# BTsoundCard_R1.net
KiCad netlist of a schematic drawn in EAGLE
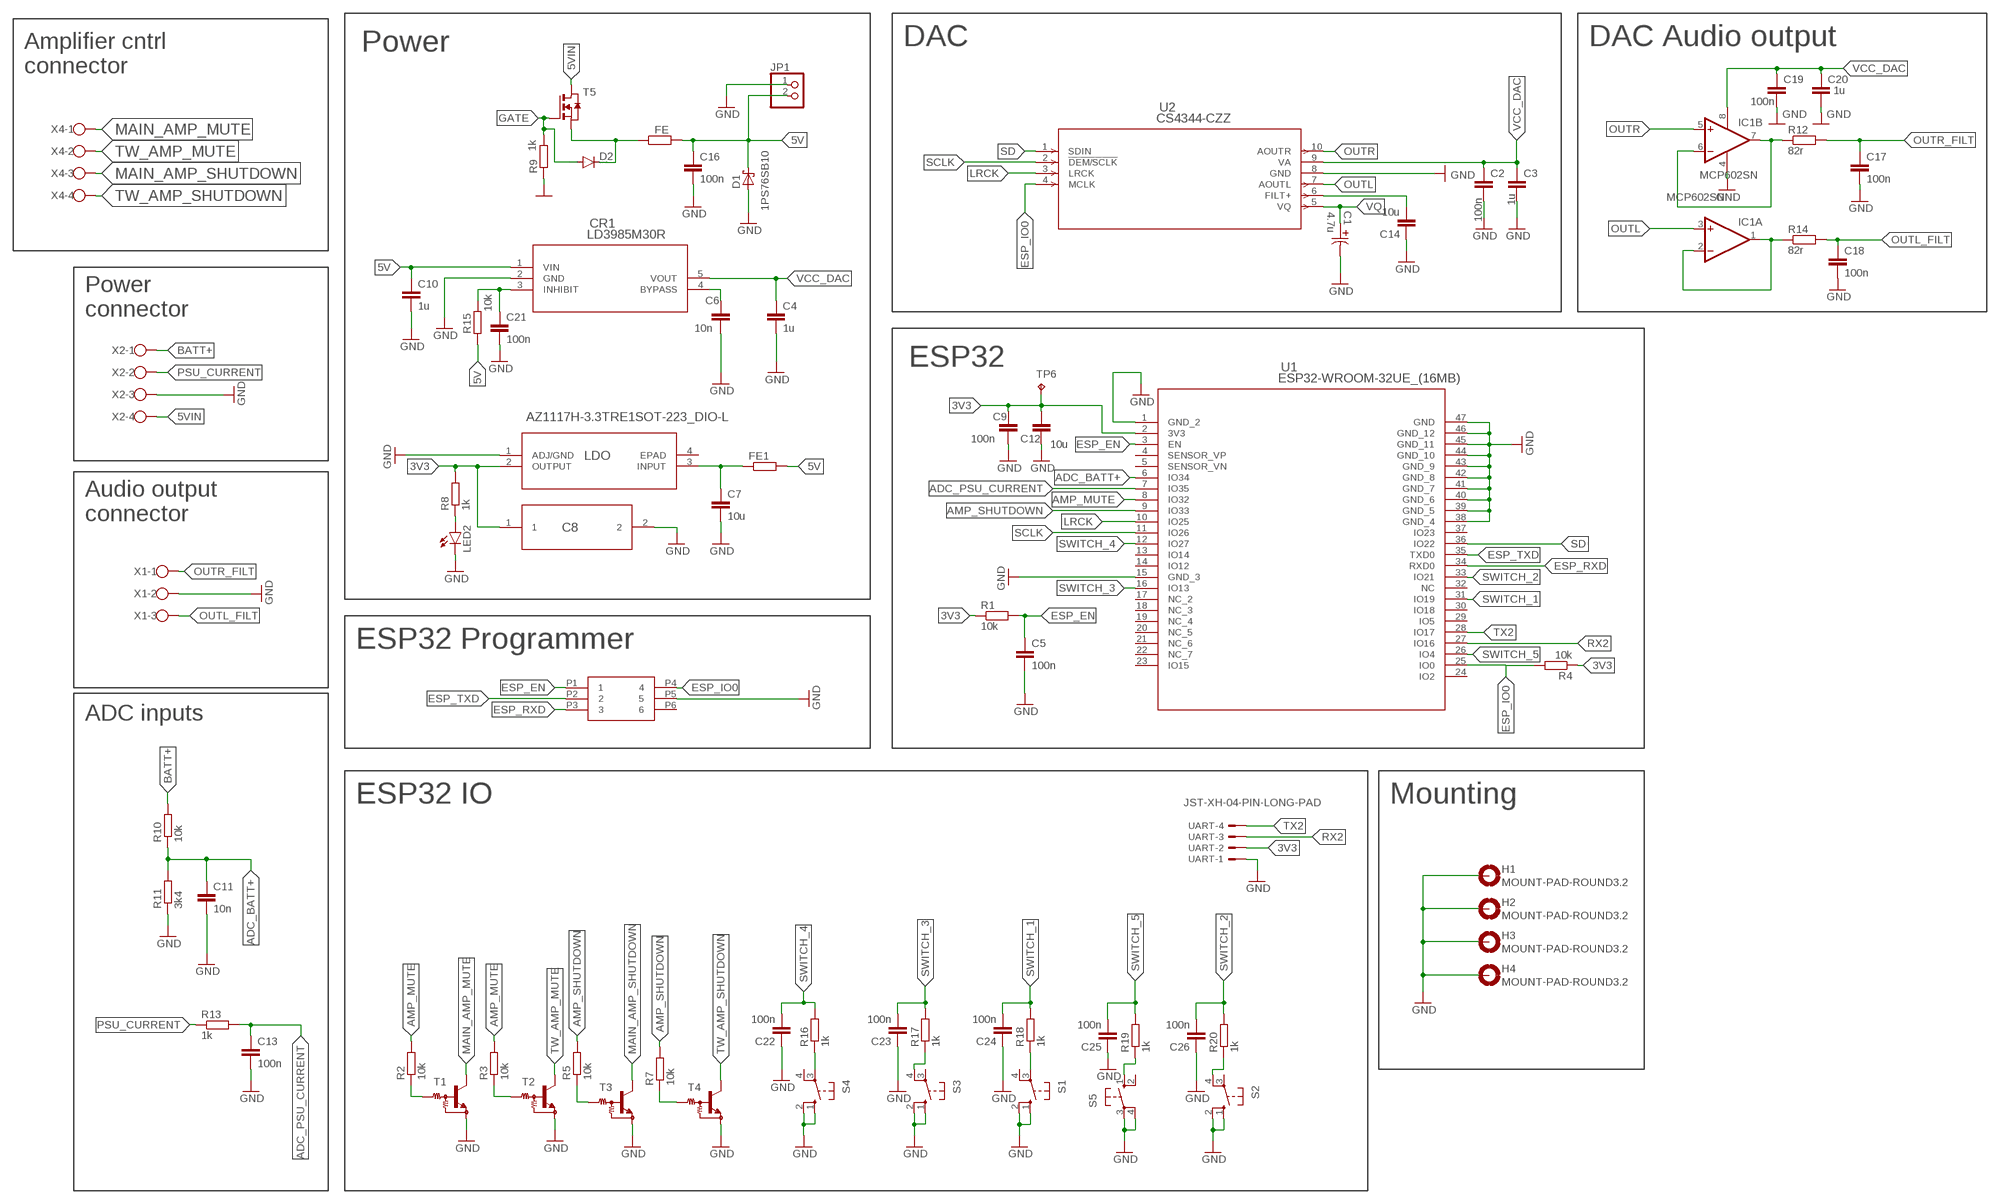
[diagram p0: schematic, sheet 1]

(export (version "E")
  (design (tool "Eeschema 10.0.6"))
  (components
    (comp (ref "C1")
      (value "4.7u")
      (footprint "eagle-import:CAP_EEFK_B_PAN-M")
      (fields (field (name "MANUFACTURER_PART_NUMBER") "EEEFK1H4R7R"))
      (libsource (lib "eagle-import") (part "EEEFK1H4R7RCAP_EEFK_B_PAN-M"))
    )
    (comp (ref "C2")
      (value "100n")
      (footprint "eagle-import:C0603")
      (libsource (lib "eagle-import") (part "C-EUC0603"))
    )
    (comp (ref "C3")
      (value "1u")
      (footprint "eagle-import:C0603")
      (libsource (lib "eagle-import") (part "C-EUC0603"))
    )
    (comp (ref "C4")
      (value "1u")
      (footprint "eagle-import:C0603")
      (libsource (lib "eagle-import") (part "C-EUC0603"))
    )
    (comp (ref "C5")
      (value "100n")
      (footprint "eagle-import:C0603")
      (libsource (lib "eagle-import") (part "C-EUC0603"))
    )
    (comp (ref "C6")
      (value "10n")
      (footprint "eagle-import:C0603")
      (libsource (lib "eagle-import") (part "C-EUC0603"))
    )
    (comp (ref "C7")
      (value "10u")
      (footprint "eagle-import:C0805")
      (libsource (lib "eagle-import") (part "C-EUC0805"))
    )
    (comp (ref "C8")
      (value "TPSC336K010R0375")
      (footprint "eagle-import:TPSC336K010R0375_AVX")
      (fields (field (name "COPYRIGHT") "Copyright (C) 2018 Accelerated Designs. All rights reserved"))
      (libsource (lib "eagle-import") (part "TPSC336K010R0375"))
    )
    (comp (ref "C9")
      (value "100n")
      (footprint "eagle-import:C0603")
      (libsource (lib "eagle-import") (part "C-EUC0603"))
    )
    (comp (ref "C10")
      (value "1u")
      (footprint "eagle-import:C0603")
      (libsource (lib "eagle-import") (part "C-EUC0603"))
    )
    (comp (ref "C11")
      (value "10n")
      (footprint "eagle-import:C0603")
      (libsource (lib "eagle-import") (part "C-EUC0603"))
    )
    (comp (ref "C12")
      (value "10u")
      (footprint "eagle-import:C0805")
      (libsource (lib "eagle-import") (part "C-EUC0805"))
    )
    (comp (ref "C13")
      (value "100n")
      (footprint "eagle-import:C0603")
      (libsource (lib "eagle-import") (part "C-EUC0603"))
    )
    (comp (ref "C14")
      (value "10u")
      (footprint "eagle-import:C0805")
      (libsource (lib "eagle-import") (part "C-EUC0805"))
    )
    (comp (ref "C16")
      (value "100n")
      (footprint "eagle-import:C0603")
      (libsource (lib "eagle-import") (part "C-EUC0603"))
    )
    (comp (ref "C17")
      (value "100n")
      (footprint "eagle-import:C0603")
      (libsource (lib "eagle-import") (part "C-EUC0603"))
    )
    (comp (ref "C18")
      (value "100n")
      (footprint "eagle-import:C0603")
      (libsource (lib "eagle-import") (part "C-EUC0603"))
    )
    (comp (ref "C19")
      (value "100n")
      (footprint "eagle-import:C0603")
      (libsource (lib "eagle-import") (part "C-EUC0603"))
    )
    (comp (ref "C20")
      (value "1u")
      (footprint "eagle-import:C0603")
      (libsource (lib "eagle-import") (part "C-EUC0603"))
    )
    (comp (ref "C21")
      (value "100n")
      (footprint "eagle-import:C0603")
      (libsource (lib "eagle-import") (part "C-EUC0603"))
    )
    (comp (ref "C22")
      (value "100n")
      (footprint "eagle-import:C0603")
      (libsource (lib "eagle-import") (part "C-EUC0603"))
    )
    (comp (ref "C23")
      (value "100n")
      (footprint "eagle-import:C0603")
      (libsource (lib "eagle-import") (part "C-EUC0603"))
    )
    (comp (ref "C24")
      (value "100n")
      (footprint "eagle-import:C0603")
      (libsource (lib "eagle-import") (part "C-EUC0603"))
    )
    (comp (ref "C25")
      (value "100n")
      (footprint "eagle-import:C0603")
      (libsource (lib "eagle-import") (part "C-EUC0603"))
    )
    (comp (ref "C26")
      (value "100n")
      (footprint "eagle-import:C0603")
      (libsource (lib "eagle-import") (part "C-EUC0603"))
    )
    (comp (ref "CR1")
      (value "LD3985M30R")
      (footprint "eagle-import:SOT23-5L_STM")
      (fields (field (name "COPYRIGHT") "Copyright (C) 2023 Ultra Librarian. All rights reserved."))
      (libsource (lib "eagle-import") (part "LD3985M30R"))
    )
    (comp (ref "D1")
      (value "1PS76SB10")
      (footprint "eagle-import:SOD323(F)")
      (libsource (lib "eagle-import") (part "1PS76SB10"))
    )
    (comp (ref "D2")
      (value "5.1V")
      (footprint "eagle-import:MINIMELF")
      (libsource (lib "eagle-import") (part "DIODE-MINIMELF"))
    )
    (comp (ref "FE")
      (value "R-EU_R0805")
      (footprint "eagle-import:R0805")
      (libsource (lib "eagle-import") (part "R-EU_R0805"))
    )
    (comp (ref "FE1")
      (value "R-EU_R0805")
      (footprint "eagle-import:R0805")
      (libsource (lib "eagle-import") (part "R-EU_R0805"))
    )
    (comp (ref "H1")
      (value "MOUNT-PAD-ROUND3.2")
      (footprint "eagle-import:3,2-PAD")
      (libsource (lib "eagle-import") (part "MOUNT-PAD-ROUND3.2"))
    )
    (comp (ref "H2")
      (value "MOUNT-PAD-ROUND3.2")
      (footprint "eagle-import:3,2-PAD")
      (libsource (lib "eagle-import") (part "MOUNT-PAD-ROUND3.2"))
    )
    (comp (ref "H3")
      (value "MOUNT-PAD-ROUND3.2")
      (footprint "eagle-import:3,2-PAD")
      (libsource (lib "eagle-import") (part "MOUNT-PAD-ROUND3.2"))
    )
    (comp (ref "H4")
      (value "MOUNT-PAD-ROUND3.2")
      (footprint "eagle-import:3,2-PAD")
      (libsource (lib "eagle-import") (part "MOUNT-PAD-ROUND3.2"))
    )
    (comp (ref "IC1")
      (value "MCP602SN")
      (footprint "eagle-import:SO08")
      (libsource (lib "eagle-import") (part "MCP602SN"))
    )
    (comp (ref "JP1")
      (value "PINHD-1X2")
      (footprint "eagle-import:1X02")
      (libsource (lib "eagle-import") (part "PINHD-1X2"))
    )
    (comp (ref "LDO")
      (value "AZ1117H-3.3TRE1SOT-223_DIO-L")
      (footprint "eagle-import:SOT-223_DIO-L")
      (fields (field (name "MANUFACTURER_PART_NUMBER") "AZ1117H-3.3TRE1"))
      (libsource (lib "eagle-import") (part "AZ1117H-3.3TRE1SOT-223_DIO-L"))
    )
    (comp (ref "LED2")
      (value "LEDCHIP-LED0603")
      (footprint "eagle-import:CHIP-LED0603")
      (libsource (lib "eagle-import") (part "LEDCHIP-LED0603"))
    )
    (comp (ref "R1")
      (value "10k")
      (footprint "eagle-import:R0603")
      (libsource (lib "eagle-import") (part "R-EU_R0603"))
    )
    (comp (ref "R2")
      (value "10k")
      (footprint "eagle-import:R0603")
      (libsource (lib "eagle-import") (part "R-EU_R0603"))
    )
    (comp (ref "R3")
      (value "10k")
      (footprint "eagle-import:R0603")
      (libsource (lib "eagle-import") (part "R-EU_R0603"))
    )
    (comp (ref "R4")
      (value "10k")
      (footprint "eagle-import:R0603")
      (libsource (lib "eagle-import") (part "R-EU_R0603"))
    )
    (comp (ref "R5")
      (value "10k")
      (footprint "eagle-import:R0603")
      (libsource (lib "eagle-import") (part "R-EU_R0603"))
    )
    (comp (ref "R7")
      (value "10k")
      (footprint "eagle-import:R0603")
      (libsource (lib "eagle-import") (part "R-EU_R0603"))
    )
    (comp (ref "R8")
      (value "1k")
      (footprint "eagle-import:R0603")
      (libsource (lib "eagle-import") (part "R-EU_R0603"))
    )
    (comp (ref "R9")
      (value "1k")
      (footprint "eagle-import:R1206")
      (libsource (lib "eagle-import") (part "R-EU_R1206"))
    )
    (comp (ref "R10")
      (value "10k")
      (footprint "eagle-import:R0805")
      (libsource (lib "eagle-import") (part "R-EU_R0805"))
    )
    (comp (ref "R11")
      (value "3k4")
      (footprint "eagle-import:R0603")
      (libsource (lib "eagle-import") (part "R-EU_R0603"))
    )
    (comp (ref "R12")
      (value "82r")
      (footprint "eagle-import:R1206")
      (libsource (lib "eagle-import") (part "R-EU_R1206"))
    )
    (comp (ref "R13")
      (value "1k")
      (footprint "eagle-import:R0603")
      (libsource (lib "eagle-import") (part "R-EU_R0603"))
    )
    (comp (ref "R14")
      (value "82r")
      (footprint "eagle-import:R1206")
      (libsource (lib "eagle-import") (part "R-EU_R1206"))
    )
    (comp (ref "R15")
      (value "10k")
      (footprint "eagle-import:R0603")
      (libsource (lib "eagle-import") (part "R-EU_R0603"))
    )
    (comp (ref "R16")
      (value "1k")
      (footprint "eagle-import:R0603")
      (libsource (lib "eagle-import") (part "R-EU_R0603"))
    )
    (comp (ref "R17")
      (value "1k")
      (footprint "eagle-import:R0603")
      (libsource (lib "eagle-import") (part "R-EU_R0603"))
    )
    (comp (ref "R18")
      (value "1k")
      (footprint "eagle-import:R0603")
      (libsource (lib "eagle-import") (part "R-EU_R0603"))
    )
    (comp (ref "R19")
      (value "1k")
      (footprint "eagle-import:R0603")
      (libsource (lib "eagle-import") (part "R-EU_R0603"))
    )
    (comp (ref "R20")
      (value "1k")
      (footprint "eagle-import:R0603")
      (libsource (lib "eagle-import") (part "R-EU_R0603"))
    )
    (comp (ref "S1")
      (value "10-XX")
      (footprint "eagle-import:B3F-10XX")
      (fields (field (name "MPN") "B3F-1000"))
      (libsource (lib "eagle-import") (part "10-XX"))
    )
    (comp (ref "S2")
      (value "10-XX")
      (footprint "eagle-import:B3F-10XX")
      (fields (field (name "MPN") "B3F-1000"))
      (libsource (lib "eagle-import") (part "10-XX"))
    )
    (comp (ref "S3")
      (value "10-XX")
      (footprint "eagle-import:B3F-10XX")
      (fields (field (name "MPN") "B3F-1000"))
      (libsource (lib "eagle-import") (part "10-XX"))
    )
    (comp (ref "S4")
      (value "10-XX")
      (footprint "eagle-import:B3F-10XX")
      (fields (field (name "MPN") "B3F-1000"))
      (libsource (lib "eagle-import") (part "10-XX"))
    )
    (comp (ref "S5")
      (value "10-XX")
      (footprint "eagle-import:B3F-10XX")
      (fields (field (name "MPN") "B3F-1000"))
      (libsource (lib "eagle-import") (part "10-XX"))
    )
    (comp (ref "T1")
      (value "MUN2212T1-NPN_DRIVER-SC59-BEC")
      (footprint "eagle-import:SC59-BEC")
      (libsource (lib "eagle-import") (part "-NPN_DRIVER-SC59-BECMUN2212T1"))
    )
    (comp (ref "T2")
      (value "MUN2212T1-NPN_DRIVER-SC59-BEC")
      (footprint "eagle-import:SC59-BEC")
      (libsource (lib "eagle-import") (part "-NPN_DRIVER-SC59-BECMUN2212T1"))
    )
    (comp (ref "T3")
      (value "MUN2212T1-NPN_DRIVER-SC59-BEC")
      (footprint "eagle-import:SC59-BEC")
      (libsource (lib "eagle-import") (part "-NPN_DRIVER-SC59-BECMUN2212T1"))
    )
    (comp (ref "T4")
      (value "MUN2212T1-NPN_DRIVER-SC59-BEC")
      (footprint "eagle-import:SC59-BEC")
      (libsource (lib "eagle-import") (part "-NPN_DRIVER-SC59-BECMUN2212T1"))
    )
    (comp (ref "T5")
      (value "NMOSSOT23")
      (footprint "eagle-import:SOT-23")
      (libsource (lib "eagle-import") (part "NMOSSOT23"))
    )
    (comp (ref "TP6")
      (value "TPPAD1-13")
      (footprint "eagle-import:P1-13")
      (libsource (lib "eagle-import") (part "TPPAD1-13"))
    )
    (comp (ref "U$3")
      (value "3X2")
      (footprint "eagle-import:2X3")
      (libsource (lib "eagle-import") (part "3X2"))
    )
    (comp (ref "U1")
      (value "ESP32-WROOM-32UE_(16MB)")
      (footprint "eagle-import:IC38_ESP32-WROOM-32UE_(16MB)_E")
      (fields
        (field (name "MANUFACTURER_PART_NUMBER") "ESP32-WROOM-32UE (16MB)")
        (field (name "COPYRIGHT") "Copyright (C) 2022 Ultra Librarian. All rights reserved.")
      )
      (libsource (lib "eagle-import") (part "ESP32-WROOM-32UE_(16MB)"))
    )
    (comp (ref "U2")
      (value "CS4344-CZZ")
      (footprint "eagle-import:CIR-TSSOP-10")
      (fields (field (name "COPYRIGHT") "Copyright (C) 2023 Ultra Librarian. All rights reserved."))
      (libsource (lib "eagle-import") (part "CS4344-CZZ"))
    )
    (comp (ref "UART")
      (value "JST-XH-04-PIN-LONG-PAD")
      (footprint "eagle-import:JST-XH-04-PACKAGE-LONG-PAD")
      (libsource (lib "eagle-import") (part "JST-XH-04-PIN-LONG-PAD"))
    )
    (comp (ref "X1")
      (value "W237-103")
      (footprint "eagle-import:W237-103")
      (fields (field (name "MPN") "237-103"))
      (libsource (lib "eagle-import") (part "W237-103"))
    )
    (comp (ref "X2")
      (value "W237-4")
      (footprint "eagle-import:W237-4")
      (libsource (lib "eagle-import") (part "W237-4"))
    )
    (comp (ref "X4")
      (value "W237-4")
      (footprint "eagle-import:W237-4")
      (libsource (lib "eagle-import") (part "W237-4"))
    )
  )
  (nets
    (net (code "1") (name "3V3") (class "Default")
      (node (ref "C12") (pin "2") (pinfunction "2_2") (pintype "passive"))
      (node (ref "C8") (pin "1") (pinfunction "1_1") (pintype "passive"))
      (node (ref "C9") (pin "1") (pinfunction "1_1") (pintype "passive"))
      (node (ref "LDO") (pin "2") (pinfunction "OUTPUT_2") (pintype "output"))
      (node (ref "R1") (pin "1") (pinfunction "1_1") (pintype "passive"))
      (node (ref "R4") (pin "1") (pinfunction "1_1") (pintype "passive"))
      (node (ref "R8") (pin "2") (pinfunction "2_2") (pintype "passive"))
      (node (ref "TP6") (pin "TP") (pinfunction "TP_TP") (pintype "input"))
      (node (ref "U1") (pin "2") (pinfunction "3V3_2") (pintype "passive"))
      (node (ref "UART") (pin "2") (pinfunction "S_2") (pintype "passive"))
    )
    (net (code "2") (name "5V") (class "Default")
      (node (ref "C10") (pin "1") (pinfunction "1_1") (pintype "passive"))
      (node (ref "C16") (pin "1") (pinfunction "1_1") (pintype "passive"))
      (node (ref "CR1") (pin "1") (pinfunction "VIN_1") (pintype "power_in"))
      (node (ref "D1") (pin "1") (pinfunction "K_1") (pintype "passive"))
      (node (ref "FE") (pin "2") (pinfunction "2_2") (pintype "passive"))
      (node (ref "FE1") (pin "2") (pinfunction "2_2") (pintype "passive"))
      (node (ref "JP1") (pin "2") (pinfunction "2_2") (pintype "passive"))
      (node (ref "R15") (pin "1") (pinfunction "1_1") (pintype "passive"))
    )
    (net (code "3") (name "5VIN") (class "Default")
      (node (ref "T5") (pin "1") (pinfunction "D_1") (pintype "passive"))
      (node (ref "X2") (pin "4") (pinfunction "KL_4") (pintype "passive"))
    )
    (net (code "4") (name "ADC_BATT+") (class "Default")
      (node (ref "C11") (pin "1") (pinfunction "1_1") (pintype "passive"))
      (node (ref "R10") (pin "1") (pinfunction "1_1") (pintype "passive"))
      (node (ref "R11") (pin "2") (pinfunction "2_2") (pintype "passive"))
      (node (ref "U1") (pin "6") (pinfunction "IO34_6") (pintype "passive"))
    )
    (net (code "5") (name "ADC_PSU_CURRENT") (class "Default")
      (node (ref "C13") (pin "1") (pinfunction "1_1") (pintype "passive"))
      (node (ref "R13") (pin "2") (pinfunction "2_2") (pintype "passive"))
      (node (ref "U1") (pin "7") (pinfunction "IO35_7") (pintype "passive"))
    )
    (net (code "6") (name "AMP_MUTE") (class "Default")
      (node (ref "R2") (pin "2") (pinfunction "2_2") (pintype "passive"))
      (node (ref "R3") (pin "2") (pinfunction "2_2") (pintype "passive"))
      (node (ref "U1") (pin "8") (pinfunction "IO32_8") (pintype "passive"))
    )
    (net (code "7") (name "AMP_SHUTDOWN") (class "Default")
      (node (ref "R5") (pin "2") (pinfunction "2_2") (pintype "passive"))
      (node (ref "R7") (pin "2") (pinfunction "2_2") (pintype "passive"))
      (node (ref "U1") (pin "9") (pinfunction "IO33_9") (pintype "passive"))
    )
    (net (code "8") (name "BATT+") (class "Default")
      (node (ref "R10") (pin "2") (pinfunction "2_2") (pintype "passive"))
      (node (ref "X2") (pin "1") (pinfunction "KL_1") (pintype "passive"))
    )
    (net (code "9") (name "ESP_EN") (class "Default")
      (node (ref "C5") (pin "1") (pinfunction "1_1") (pintype "passive"))
      (node (ref "R1") (pin "2") (pinfunction "2_2") (pintype "passive"))
      (node (ref "U$3") (pin "P1") (pinfunction "1_P1") (pintype "bidirectional"))
      (node (ref "U1") (pin "3") (pinfunction "EN_3") (pintype "passive"))
    )
    (net (code "10") (name "ESP_IO0") (class "Default")
      (node (ref "R4") (pin "2") (pinfunction "2_2") (pintype "passive"))
      (node (ref "U$3") (pin "P4") (pinfunction "4_P4") (pintype "bidirectional"))
      (node (ref "U1") (pin "25") (pinfunction "IO0_25") (pintype "passive"))
      (node (ref "U2") (pin "4") (pinfunction "MCLK_4") (pintype "input"))
    )
    (net (code "11") (name "ESP_RXD") (class "Default")
      (node (ref "U$3") (pin "P3") (pinfunction "3_P3") (pintype "bidirectional"))
      (node (ref "U1") (pin "34") (pinfunction "RXD0_34") (pintype "passive"))
    )
    (net (code "12") (name "ESP_TXD") (class "Default")
      (node (ref "U$3") (pin "P2") (pinfunction "2_P2") (pintype "bidirectional"))
      (node (ref "U1") (pin "35") (pinfunction "TXD0_35") (pintype "passive"))
    )
    (net (code "13") (name "GATE") (class "Default")
      (node (ref "D2") (pin "A") (pinfunction "A_A") (pintype "passive"))
      (node (ref "R9") (pin "2") (pinfunction "2_2") (pintype "passive"))
      (node (ref "T5") (pin "3") (pinfunction "G_3") (pintype "passive"))
    )
    (net (code "14") (name "GND") (class "Default")
      (node (ref "C1") (pin "2") (pinfunction "2_2") (pintype "passive"))
      (node (ref "C10") (pin "2") (pinfunction "2_2") (pintype "passive"))
      (node (ref "C11") (pin "2") (pinfunction "2_2") (pintype "passive"))
      (node (ref "C12") (pin "1") (pinfunction "1_1") (pintype "passive"))
      (node (ref "C13") (pin "2") (pinfunction "2_2") (pintype "passive"))
      (node (ref "C14") (pin "1") (pinfunction "1_1") (pintype "passive"))
      (node (ref "C16") (pin "2") (pinfunction "2_2") (pintype "passive"))
      (node (ref "C17") (pin "2") (pinfunction "2_2") (pintype "passive"))
      (node (ref "C18") (pin "2") (pinfunction "2_2") (pintype "passive"))
      (node (ref "C19") (pin "2") (pinfunction "2_2") (pintype "passive"))
      (node (ref "C2") (pin "2") (pinfunction "2_2") (pintype "passive"))
      (node (ref "C20") (pin "2") (pinfunction "2_2") (pintype "passive"))
      (node (ref "C21") (pin "2") (pinfunction "2_2") (pintype "passive"))
      (node (ref "C22") (pin "1") (pinfunction "1_1") (pintype "passive"))
      (node (ref "C23") (pin "1") (pinfunction "1_1") (pintype "passive"))
      (node (ref "C24") (pin "1") (pinfunction "1_1") (pintype "passive"))
      (node (ref "C25") (pin "1") (pinfunction "1_1") (pintype "passive"))
      (node (ref "C26") (pin "1") (pinfunction "1_1") (pintype "passive"))
      (node (ref "C3") (pin "2") (pinfunction "2_2") (pintype "passive"))
      (node (ref "C4") (pin "2") (pinfunction "2_2") (pintype "passive"))
      (node (ref "C5") (pin "2") (pinfunction "2_2") (pintype "passive"))
      (node (ref "C6") (pin "2") (pinfunction "2_2") (pintype "passive"))
      (node (ref "C7") (pin "2") (pinfunction "2_2") (pintype "passive"))
      (node (ref "C8") (pin "2") (pinfunction "2_2") (pintype "passive"))
      (node (ref "C9") (pin "2") (pinfunction "2_2") (pintype "passive"))
      (node (ref "CR1") (pin "2") (pinfunction "GND_2") (pintype "passive"))
      (node (ref "D1") (pin "2") (pinfunction "A_2") (pintype "passive"))
      (node (ref "H1") (pin "B3,2") (pinfunction "MOUNT_B3,2") (pintype "passive"))
      (node (ref "H2") (pin "B3,2") (pinfunction "MOUNT_B3,2") (pintype "passive"))
      (node (ref "H3") (pin "B3,2") (pinfunction "MOUNT_B3,2") (pintype "passive"))
      (node (ref "H4") (pin "B3,2") (pinfunction "MOUNT_B3,2") (pintype "passive"))
      (node (ref "IC1") (pin "4") (pinfunction "V-_4") (pintype "power_in"))
      (node (ref "JP1") (pin "1") (pinfunction "1_1") (pintype "passive"))
      (node (ref "LDO") (pin "1") (pinfunction "ADJ/GND_1") (pintype "bidirectional"))
      (node (ref "LED2") (pin "C") (pinfunction "C_C") (pintype "passive"))
      (node (ref "R11") (pin "1") (pinfunction "1_1") (pintype "passive"))
      (node (ref "R9") (pin "1") (pinfunction "1_1") (pintype "passive"))
      (node (ref "S1") (pin "1") (pinfunction "S_1") (pintype "passive"))
      (node (ref "S1") (pin "2") (pinfunction "S1_2") (pintype "passive"))
      (node (ref "S2") (pin "1") (pinfunction "S_1") (pintype "passive"))
      (node (ref "S2") (pin "2") (pinfunction "S1_2") (pintype "passive"))
      (node (ref "S3") (pin "1") (pinfunction "S_1") (pintype "passive"))
      (node (ref "S3") (pin "2") (pinfunction "S1_2") (pintype "passive"))
      (node (ref "S4") (pin "1") (pinfunction "S_1") (pintype "passive"))
      (node (ref "S4") (pin "2") (pinfunction "S1_2") (pintype "passive"))
      (node (ref "S5") (pin "3") (pinfunction "P_3") (pintype "passive"))
      (node (ref "S5") (pin "4") (pinfunction "P1_4") (pintype "passive"))
      (node (ref "T1") (pin "E") (pinfunction "E_E") (pintype "passive"))
      (node (ref "T2") (pin "E") (pinfunction "E_E") (pintype "passive"))
      (node (ref "T3") (pin "E") (pinfunction "E_E") (pintype "passive"))
      (node (ref "T4") (pin "E") (pinfunction "E_E") (pintype "passive"))
      (node (ref "U$3") (pin "P5") (pinfunction "5_P5") (pintype "bidirectional"))
      (node (ref "U1") (pin "1") (pinfunction "GND_2_1") (pintype "passive"))
      (node (ref "U1") (pin "15") (pinfunction "GND_3_15") (pintype "passive"))
      (node (ref "U1") (pin "38") (pinfunction "GND_4_38") (pintype "passive"))
      (node (ref "U1") (pin "39") (pinfunction "GND_5_39") (pintype "passive"))
      (node (ref "U1") (pin "40") (pinfunction "GND_6_40") (pintype "passive"))
      (node (ref "U1") (pin "41") (pinfunction "GND_7_41") (pintype "passive"))
      (node (ref "U1") (pin "42") (pinfunction "GND_8_42") (pintype "passive"))
      (node (ref "U1") (pin "43") (pinfunction "GND_9_43") (pintype "passive"))
      (node (ref "U1") (pin "44") (pinfunction "GND_10_44") (pintype "passive"))
      (node (ref "U1") (pin "45") (pinfunction "GND_11_45") (pintype "passive"))
      (node (ref "U1") (pin "46") (pinfunction "GND_12_46") (pintype "passive"))
      (node (ref "U1") (pin "47") (pinfunction "GND_47") (pintype "passive"))
      (node (ref "U2") (pin "8") (pinfunction "GND_8") (pintype "power_in"))
      (node (ref "UART") (pin "1") (pinfunction "S_1") (pintype "passive"))
      (node (ref "X1") (pin "2") (pinfunction "KL_2") (pintype "passive"))
      (node (ref "X2") (pin "3") (pinfunction "KL_3") (pintype "passive"))
    )
    (net (code "15") (name "LRCK") (class "Default")
      (node (ref "U1") (pin "10") (pinfunction "IO25_10") (pintype "passive"))
      (node (ref "U2") (pin "3") (pinfunction "LRCK_3") (pintype "input"))
    )
    (net (code "16") (name "MAIN_AMP_MUTE") (class "Default")
      (node (ref "T1") (pin "C") (pinfunction "C_C") (pintype "passive"))
      (node (ref "X4") (pin "1") (pinfunction "KL_1") (pintype "passive"))
    )
    (net (code "17") (name "MAIN_AMP_SHUTDOWN") (class "Default")
      (node (ref "T3") (pin "C") (pinfunction "C_C") (pintype "passive"))
      (node (ref "X4") (pin "3") (pinfunction "KL_3") (pintype "passive"))
    )
    (net (code "18") (name "Net-(CR1-BYPASS)") (class "Default")
      (node (ref "C6") (pin "1") (pinfunction "1_1") (pintype "passive"))
      (node (ref "CR1") (pin "4") (pinfunction "BYPASS_4") (pintype "passive"))
    )
    (net (code "19") (name "Net-(CR1-INHIBIT)") (class "Default")
      (node (ref "C21") (pin "1") (pinfunction "1_1") (pintype "passive"))
      (node (ref "CR1") (pin "3") (pinfunction "INHIBIT_3") (pintype "input"))
      (node (ref "R15") (pin "2") (pinfunction "2_2") (pintype "passive"))
    )
    (net (code "20") (name "Net-(IC1A--IN)") (class "Default")
      (node (ref "IC1") (pin "1") (pinfunction "OUT_1") (pintype "output"))
      (node (ref "IC1") (pin "2") (pinfunction "-IN_2") (pintype "input"))
      (node (ref "R14") (pin "1") (pinfunction "1_1") (pintype "passive"))
    )
    (net (code "21") (name "Net-(IC1B--IN)") (class "Default")
      (node (ref "IC1") (pin "6") (pinfunction "-IN_6") (pintype "input"))
      (node (ref "IC1") (pin "7") (pinfunction "OUT_7") (pintype "output"))
      (node (ref "R12") (pin "1") (pinfunction "1_1") (pintype "passive"))
    )
    (net (code "22") (name "Net-(LDO-INPUT)") (class "Default")
      (node (ref "C7") (pin "1") (pinfunction "1_1") (pintype "passive"))
      (node (ref "FE1") (pin "1") (pinfunction "1_1") (pintype "passive"))
      (node (ref "LDO") (pin "3") (pinfunction "INPUT_3") (pintype "input"))
    )
    (net (code "23") (name "Net-(LED2-PadA)") (class "Default")
      (node (ref "LED2") (pin "A") (pinfunction "A_A") (pintype "passive"))
      (node (ref "R8") (pin "1") (pinfunction "1_1") (pintype "passive"))
    )
    (net (code "24") (name "Net-(R2-Pad1)") (class "Default")
      (node (ref "R2") (pin "1") (pinfunction "1_1") (pintype "passive"))
      (node (ref "T1") (pin "B") (pinfunction "B_B") (pintype "passive"))
    )
    (net (code "25") (name "Net-(R3-Pad1)") (class "Default")
      (node (ref "R3") (pin "1") (pinfunction "1_1") (pintype "passive"))
      (node (ref "T2") (pin "B") (pinfunction "B_B") (pintype "passive"))
    )
    (net (code "26") (name "Net-(R5-Pad1)") (class "Default")
      (node (ref "R5") (pin "1") (pinfunction "1_1") (pintype "passive"))
      (node (ref "T3") (pin "B") (pinfunction "B_B") (pintype "passive"))
    )
    (net (code "27") (name "Net-(R7-Pad1)") (class "Default")
      (node (ref "R7") (pin "1") (pinfunction "1_1") (pintype "passive"))
      (node (ref "T4") (pin "B") (pinfunction "B_B") (pintype "passive"))
    )
    (net (code "28") (name "Net-(S1-P)") (class "Default")
      (node (ref "R18") (pin "1") (pinfunction "1_1") (pintype "passive"))
      (node (ref "S1") (pin "3") (pinfunction "P_3") (pintype "passive"))
    )
    (net (code "29") (name "Net-(S2-P1)") (class "Default")
      (node (ref "R20") (pin "1") (pinfunction "1_1") (pintype "passive"))
      (node (ref "S2") (pin "4") (pinfunction "P1_4") (pintype "passive"))
    )
    (net (code "30") (name "Net-(S3-P1)") (class "Default")
      (node (ref "R17") (pin "1") (pinfunction "1_1") (pintype "passive"))
      (node (ref "S3") (pin "4") (pinfunction "P1_4") (pintype "passive"))
    )
    (net (code "31") (name "Net-(S4-P)") (class "Default")
      (node (ref "R16") (pin "1") (pinfunction "1_1") (pintype "passive"))
      (node (ref "S4") (pin "3") (pinfunction "P_3") (pintype "passive"))
    )
    (net (code "32") (name "Net-(S5-S)") (class "Default")
      (node (ref "R19") (pin "1") (pinfunction "1_1") (pintype "passive"))
      (node (ref "S5") (pin "1") (pinfunction "S_1") (pintype "passive"))
    )
    (net (code "33") (name "Net-(T5-S)") (class "Default")
      (node (ref "D2") (pin "C") (pinfunction "C_C") (pintype "passive"))
      (node (ref "FE") (pin "1") (pinfunction "1_1") (pintype "passive"))
      (node (ref "T5") (pin "2") (pinfunction "S_2") (pintype "passive"))
    )
    (net (code "34") (name "Net-(U2-FILT+)") (class "Default")
      (node (ref "C14") (pin "2") (pinfunction "2_2") (pintype "passive"))
      (node (ref "U2") (pin "6") (pinfunction "FILT+_6") (pintype "output"))
    )
    (net (code "35") (name "OUTL") (class "Default")
      (node (ref "IC1") (pin "3") (pinfunction "+IN_3") (pintype "input"))
      (node (ref "U2") (pin "7") (pinfunction "AOUTL_7") (pintype "output"))
    )
    (net (code "36") (name "OUTL_FILT") (class "Default")
      (node (ref "C18") (pin "1") (pinfunction "1_1") (pintype "passive"))
      (node (ref "R14") (pin "2") (pinfunction "2_2") (pintype "passive"))
      (node (ref "X1") (pin "3") (pinfunction "KL_3") (pintype "passive"))
    )
    (net (code "37") (name "OUTR") (class "Default")
      (node (ref "IC1") (pin "5") (pinfunction "+IN_5") (pintype "input"))
      (node (ref "U2") (pin "10") (pinfunction "AOUTR_10") (pintype "output"))
    )
    (net (code "38") (name "OUTR_FILT") (class "Default")
      (node (ref "C17") (pin "1") (pinfunction "1_1") (pintype "passive"))
      (node (ref "R12") (pin "2") (pinfunction "2_2") (pintype "passive"))
      (node (ref "X1") (pin "1") (pinfunction "KL_1") (pintype "passive"))
    )
    (net (code "39") (name "PSU_CURRENT") (class "Default")
      (node (ref "R13") (pin "1") (pinfunction "1_1") (pintype "passive"))
      (node (ref "X2") (pin "2") (pinfunction "KL_2") (pintype "passive"))
    )
    (net (code "40") (name "RX2") (class "Default")
      (node (ref "U1") (pin "27") (pinfunction "IO16_27") (pintype "passive"))
      (node (ref "UART") (pin "3") (pinfunction "S_3") (pintype "passive"))
    )
    (net (code "41") (name "SCLK") (class "Default")
      (node (ref "U1") (pin "11") (pinfunction "IO26_11") (pintype "passive"))
      (node (ref "U2") (pin "2") (pinfunction "~{DEM/SCLK}_2") (pintype "input"))
    )
    (net (code "42") (name "SD") (class "Default")
      (node (ref "U1") (pin "36") (pinfunction "IO22_36") (pintype "passive"))
      (node (ref "U2") (pin "1") (pinfunction "SDIN_1") (pintype "input"))
    )
    (net (code "43") (name "SWITCH_1") (class "Default")
      (node (ref "C24") (pin "2") (pinfunction "2_2") (pintype "passive"))
      (node (ref "R18") (pin "2") (pinfunction "2_2") (pintype "passive"))
      (node (ref "U1") (pin "31") (pinfunction "IO19_31") (pintype "passive"))
    )
    (net (code "44") (name "SWITCH_2") (class "Default")
      (node (ref "C26") (pin "2") (pinfunction "2_2") (pintype "passive"))
      (node (ref "R20") (pin "2") (pinfunction "2_2") (pintype "passive"))
      (node (ref "U1") (pin "33") (pinfunction "IO21_33") (pintype "passive"))
    )
    (net (code "45") (name "SWITCH_3") (class "Default")
      (node (ref "C23") (pin "2") (pinfunction "2_2") (pintype "passive"))
      (node (ref "R17") (pin "2") (pinfunction "2_2") (pintype "passive"))
      (node (ref "U1") (pin "16") (pinfunction "IO13_16") (pintype "passive"))
    )
    (net (code "46") (name "SWITCH_4") (class "Default")
      (node (ref "C22") (pin "2") (pinfunction "2_2") (pintype "passive"))
      (node (ref "R16") (pin "2") (pinfunction "2_2") (pintype "passive"))
      (node (ref "U1") (pin "12") (pinfunction "IO27_12") (pintype "passive"))
    )
    (net (code "47") (name "SWITCH_5") (class "Default")
      (node (ref "C25") (pin "2") (pinfunction "2_2") (pintype "passive"))
      (node (ref "R19") (pin "2") (pinfunction "2_2") (pintype "passive"))
      (node (ref "U1") (pin "26") (pinfunction "IO4_26") (pintype "passive"))
    )
    (net (code "48") (name "TW_AMP_MUTE") (class "Default")
      (node (ref "T2") (pin "C") (pinfunction "C_C") (pintype "passive"))
      (node (ref "X4") (pin "2") (pinfunction "KL_2") (pintype "passive"))
    )
    (net (code "49") (name "TW_AMP_SHUTDOWN") (class "Default")
      (node (ref "T4") (pin "C") (pinfunction "C_C") (pintype "passive"))
      (node (ref "X4") (pin "4") (pinfunction "KL_4") (pintype "passive"))
    )
    (net (code "50") (name "TX2") (class "Default")
      (node (ref "U1") (pin "28") (pinfunction "IO17_28") (pintype "passive"))
      (node (ref "UART") (pin "4") (pinfunction "S_4") (pintype "passive"))
    )
    (net (code "51") (name "VCC_DAC") (class "Default")
      (node (ref "C19") (pin "1") (pinfunction "1_1") (pintype "passive"))
      (node (ref "C2") (pin "1") (pinfunction "1_1") (pintype "passive"))
      (node (ref "C20") (pin "1") (pinfunction "1_1") (pintype "passive"))
      (node (ref "C3") (pin "1") (pinfunction "1_1") (pintype "passive"))
      (node (ref "C4") (pin "1") (pinfunction "1_1") (pintype "passive"))
      (node (ref "CR1") (pin "5") (pinfunction "VOUT_5") (pintype "power_in"))
      (node (ref "IC1") (pin "8") (pinfunction "V+_8") (pintype "power_in"))
      (node (ref "U2") (pin "9") (pinfunction "VA_9") (pintype "power_in"))
    )
    (net (code "52") (name "VQ") (class "Default")
      (node (ref "C1") (pin "1") (pinfunction "1_1") (pintype "passive"))
      (node (ref "U2") (pin "5") (pinfunction "VQ_5") (pintype "output"))
    )
    (net (code "53") (name "unconnected-(LDO-EPAD-Pad4)") (class "Default")
      (node (ref "LDO") (pin "4") (pinfunction "EPAD_4") (pintype "passive"))
    )
    (net (code "54") (name "unconnected-(S1-P1-Pad4)") (class "Default")
      (node (ref "S1") (pin "4") (pinfunction "P1_4") (pintype "passive"))
    )
    (net (code "55") (name "unconnected-(S2-P-Pad3)") (class "Default")
      (node (ref "S2") (pin "3") (pinfunction "P_3") (pintype "passive"))
    )
    (net (code "56") (name "unconnected-(S3-P-Pad3)") (class "Default")
      (node (ref "S3") (pin "3") (pinfunction "P_3") (pintype "passive"))
    )
    (net (code "57") (name "unconnected-(S4-P1-Pad4)") (class "Default")
      (node (ref "S4") (pin "4") (pinfunction "P1_4") (pintype "passive"))
    )
    (net (code "58") (name "unconnected-(S5-S1-Pad2)") (class "Default")
      (node (ref "S5") (pin "2") (pinfunction "S1_2") (pintype "passive"))
    )
    (net (code "59") (name "unconnected-(U$3-6-PadP6)") (class "Default")
      (node (ref "U$3") (pin "P6") (pinfunction "6_P6") (pintype "bidirectional"))
    )
    (net (code "60") (name "unconnected-(U1-IO2-Pad24)") (class "Default")
      (node (ref "U1") (pin "24") (pinfunction "IO2_24") (pintype "passive"))
    )
    (net (code "61") (name "unconnected-(U1-IO5-Pad29)") (class "Default")
      (node (ref "U1") (pin "29") (pinfunction "IO5_29") (pintype "passive"))
    )
    (net (code "62") (name "unconnected-(U1-IO12-Pad14)") (class "Default")
      (node (ref "U1") (pin "14") (pinfunction "IO12_14") (pintype "passive"))
    )
    (net (code "63") (name "unconnected-(U1-IO14-Pad13)") (class "Default")
      (node (ref "U1") (pin "13") (pinfunction "IO14_13") (pintype "passive"))
    )
    (net (code "64") (name "unconnected-(U1-IO15-Pad23)") (class "Default")
      (node (ref "U1") (pin "23") (pinfunction "IO15_23") (pintype "passive"))
    )
    (net (code "65") (name "unconnected-(U1-IO18-Pad30)") (class "Default")
      (node (ref "U1") (pin "30") (pinfunction "IO18_30") (pintype "passive"))
    )
    (net (code "66") (name "unconnected-(U1-IO23-Pad37)") (class "Default")
      (node (ref "U1") (pin "37") (pinfunction "IO23_37") (pintype "passive"))
    )
    (net (code "67") (name "unconnected-(U1-NC-Pad32)") (class "Default")
      (node (ref "U1") (pin "32") (pinfunction "NC_32") (pintype "passive"))
    )
    (net (code "68") (name "unconnected-(U1-NC_2-Pad17)") (class "Default")
      (node (ref "U1") (pin "17") (pinfunction "NC_2_17") (pintype "passive"))
    )
    (net (code "69") (name "unconnected-(U1-NC_3-Pad18)") (class "Default")
      (node (ref "U1") (pin "18") (pinfunction "NC_3_18") (pintype "passive"))
    )
    (net (code "70") (name "unconnected-(U1-NC_4-Pad19)") (class "Default")
      (node (ref "U1") (pin "19") (pinfunction "NC_4_19") (pintype "passive"))
    )
    (net (code "71") (name "unconnected-(U1-NC_5-Pad20)") (class "Default")
      (node (ref "U1") (pin "20") (pinfunction "NC_5_20") (pintype "passive"))
    )
    (net (code "72") (name "unconnected-(U1-NC_6-Pad21)") (class "Default")
      (node (ref "U1") (pin "21") (pinfunction "NC_6_21") (pintype "passive"))
    )
    (net (code "73") (name "unconnected-(U1-NC_7-Pad22)") (class "Default")
      (node (ref "U1") (pin "22") (pinfunction "NC_7_22") (pintype "passive"))
    )
    (net (code "74") (name "unconnected-(U1-SENSOR_VN-Pad5)") (class "Default")
      (node (ref "U1") (pin "5") (pinfunction "SENSOR_VN_5") (pintype "passive"))
    )
    (net (code "75") (name "unconnected-(U1-SENSOR_VP-Pad4)") (class "Default")
      (node (ref "U1") (pin "4") (pinfunction "SENSOR_VP_4") (pintype "passive"))
    )
  )
)
